# Current_Sens.net
KiCad netlist of a schematic drawn in Altium Designer
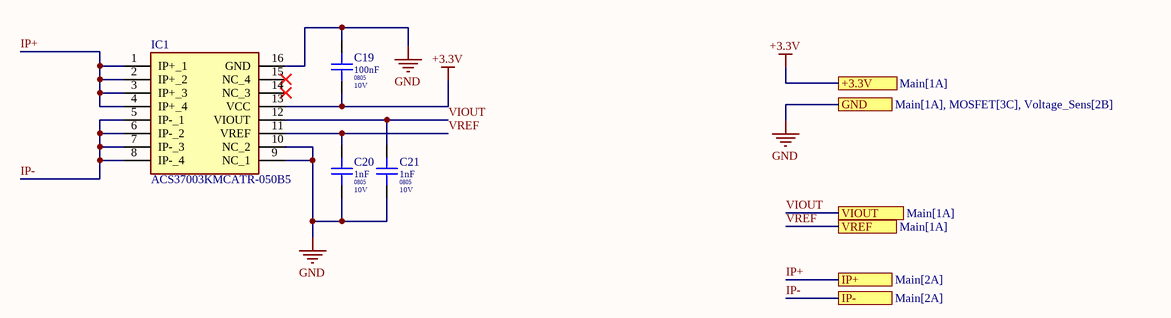
[diagram p0: Current_Sens.SchDoc]

(export (version "E")
  (design (tool "Eeschema 10.0.6"))
  (components
    (comp (ref "C19")
      (value "100nF")
      (footprint "CAPC 0805")
      (description "Capacitor Ceramic 100nF 10V 0805")
      (fields
        (field (name "TOLERANCE") "%10")
        (field (name "PACKAGE / CASE") "0805")
        (field (name "VOLTAGE") "10V")
        (field (name "PART NUMBER") "CAPC0744")
      )
      (libsource (lib "Aesk Database Library") (part "NPCapacitor"))
    )
    (comp (ref "C20")
      (value "1nF")
      (footprint "CAPC 0805")
      (description "Capacitor Ceramic 1nF 10V 0805")
      (fields
        (field (name "TOLERANCE") "%10")
        (field (name "PACKAGE / CASE") "0805")
        (field (name "VOLTAGE") "10V")
        (field (name "PART NUMBER") "CAPC0728")
      )
      (libsource (lib "Aesk Database Library") (part "NPCapacitor"))
    )
    (comp (ref "C21")
      (value "1nF")
      (footprint "CAPC 0805")
      (description "Capacitor Ceramic 1nF 10V 0805")
      (fields
        (field (name "TOLERANCE") "%10")
        (field (name "PACKAGE / CASE") "0805")
        (field (name "VOLTAGE") "10V")
        (field (name "PART NUMBER") "CAPC0728")
      )
      (libsource (lib "Aesk Database Library") (part "NPCapacitor"))
    )
    (comp (ref "IC1")
      (value "ACS37003KMCATR-050B5")
      (footprint "ACS37002LMCA050U5")
      (description "Integrated Circuit")
      (fields (field (name "MOUSER PART NUMBER") "250-03KMCATR-050B5"))
      (libsource (lib "Schlib2") (part "ACS37003KMCATR-050B5"))
    )
  )
  (nets
    (net (code "1") (name "+3.3V") (class "Default")
      (node (ref "C19") (pin "1") (pinfunction "1_1") (pintype "passive"))
      (node (ref "IC1") (pin "13") (pinfunction "VCC_13") (pintype "passive"))
    )
    (net (code "2") (name "/IP+") (class "Default")
      (node (ref "IC1") (pin "1") (pinfunction "IP+_1_1") (pintype "passive"))
      (node (ref "IC1") (pin "2") (pinfunction "IP+_2_2") (pintype "passive"))
      (node (ref "IC1") (pin "3") (pinfunction "IP+_3_3") (pintype "passive"))
      (node (ref "IC1") (pin "4") (pinfunction "IP+_4_4") (pintype "passive"))
    )
    (net (code "3") (name "/IP-") (class "Default")
      (node (ref "IC1") (pin "5") (pinfunction "IP-_1_5") (pintype "passive"))
      (node (ref "IC1") (pin "6") (pinfunction "IP-_2_6") (pintype "passive"))
      (node (ref "IC1") (pin "7") (pinfunction "IP-_3_7") (pintype "passive"))
      (node (ref "IC1") (pin "8") (pinfunction "IP-_4_8") (pintype "passive"))
    )
    (net (code "4") (name "/VIOUT") (class "Default")
      (node (ref "C21") (pin "2") (pinfunction "2_2") (pintype "passive"))
      (node (ref "IC1") (pin "12") (pinfunction "VIOUT_12") (pintype "passive"))
    )
    (net (code "5") (name "/VREF") (class "Default")
      (node (ref "C20") (pin "2") (pinfunction "2_2") (pintype "passive"))
      (node (ref "IC1") (pin "11") (pinfunction "VREF_11") (pintype "passive"))
    )
    (net (code "6") (name "GND") (class "Default")
      (node (ref "C19") (pin "2") (pinfunction "2_2") (pintype "passive"))
      (node (ref "C20") (pin "1") (pinfunction "1_1") (pintype "passive"))
      (node (ref "C21") (pin "1") (pinfunction "1_1") (pintype "passive"))
      (node (ref "IC1") (pin "10") (pinfunction "NC_2_10") (pintype "passive"))
      (node (ref "IC1") (pin "16") (pinfunction "GND_16") (pintype "passive"))
      (node (ref "IC1") (pin "9") (pinfunction "NC_1_9") (pintype "passive"))
    )
    (net (code "7") (name "unconnected-(IC1-NC_3-Pad14)") (class "Default")
      (node (ref "IC1") (pin "14") (pinfunction "NC_3_14") (pintype "passive+no_connect"))
    )
    (net (code "8") (name "unconnected-(IC1-NC_4-Pad15)") (class "Default")
      (node (ref "IC1") (pin "15") (pinfunction "NC_4_15") (pintype "passive+no_connect"))
    )
  )
)
